# AlvDuino.net
KiCad netlist of a schematic drawn in EAGLE
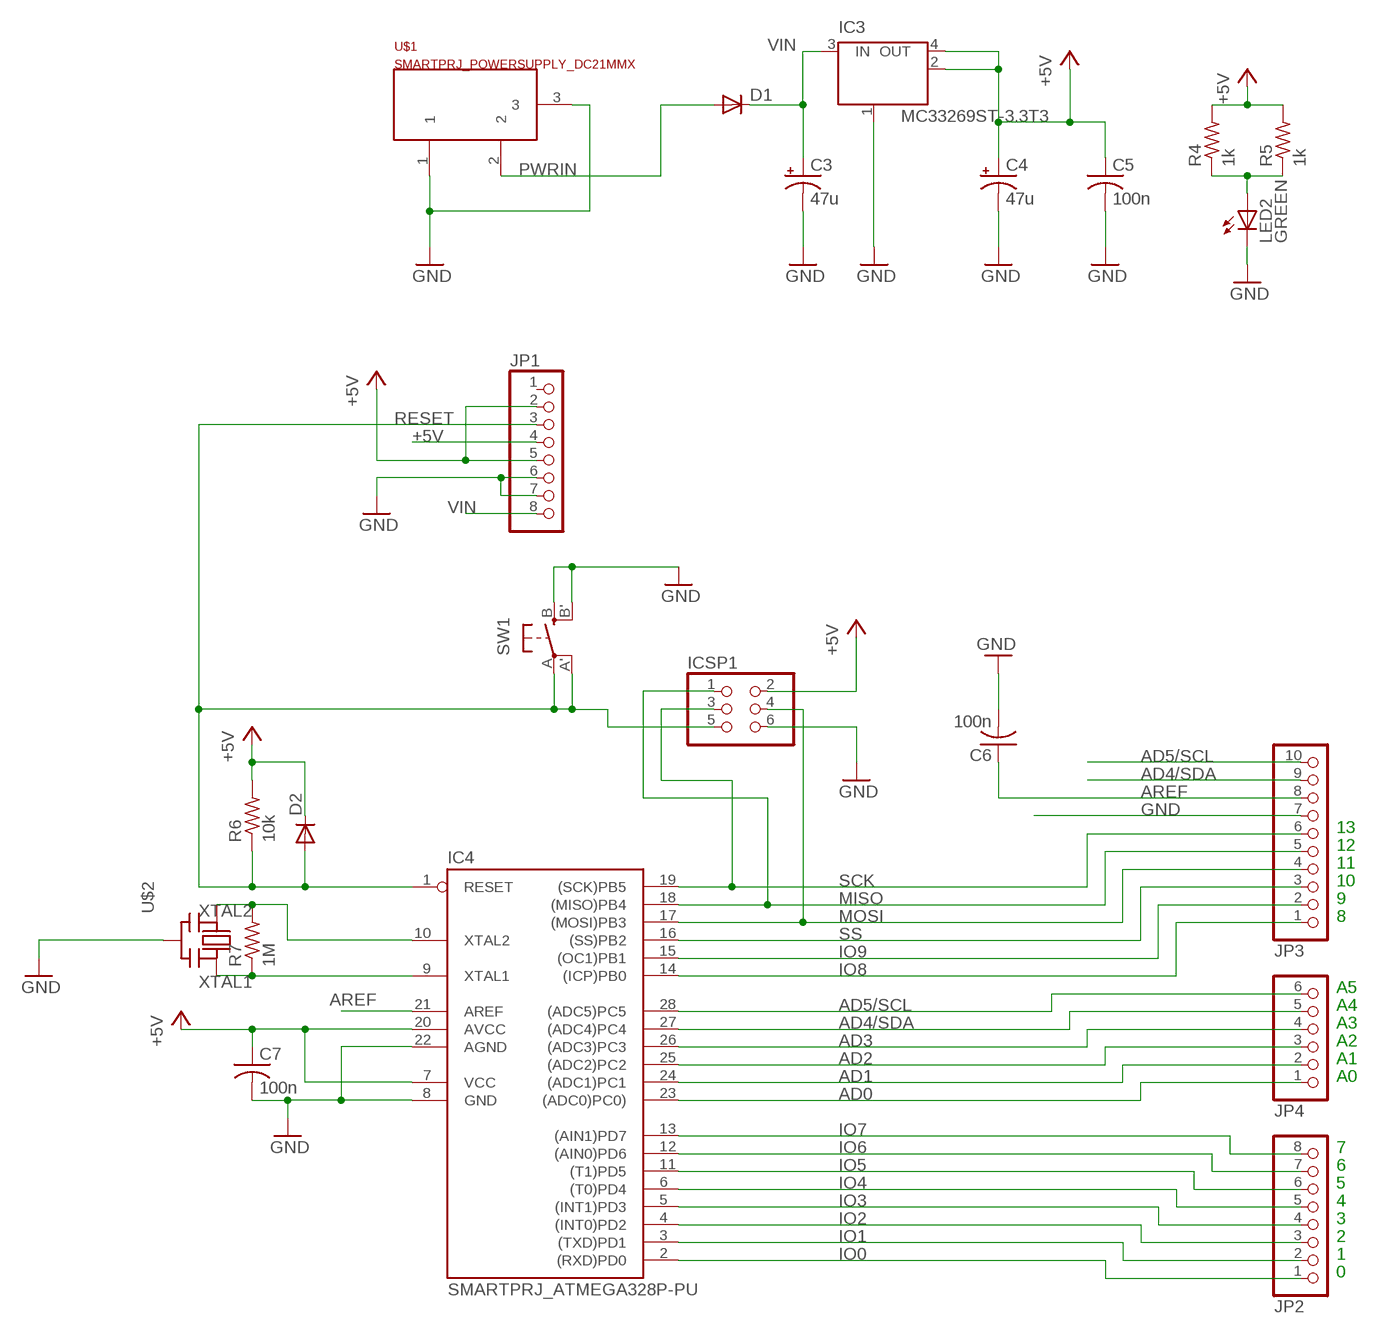
[diagram p0: schematic, sheet 1]

(export (version "E")
  (design (tool "Eeschema 10.0.6"))
  (components
    (comp (ref "C3")
      (value "47u")
      (footprint "eagle-import:PANASONIC_D")
      (libsource (lib "eagle-import") (part "CPOL-USD"))
    )
    (comp (ref "C4")
      (value "47u")
      (footprint "eagle-import:PANASONIC_D")
      (libsource (lib "eagle-import") (part "CPOL-USD"))
    )
    (comp (ref "C5")
      (value "100n")
      (footprint "eagle-import:C1206")
      (libsource (lib "eagle-import") (part "C-USC1206"))
    )
    (comp (ref "C6")
      (value "100n")
      (footprint "eagle-import:C1206")
      (libsource (lib "eagle-import") (part "C-USC1206"))
    )
    (comp (ref "C7")
      (value "100n")
      (footprint "eagle-import:C1206")
      (libsource (lib "eagle-import") (part "C-USC1206"))
    )
    (comp (ref "D1")
      (value "DIODE-DO214AA")
      (footprint "eagle-import:DO214AA")
      (libsource (lib "eagle-import") (part "DIODE-DO214AA"))
    )
    (comp (ref "D2")
      (value "DIODE-DO214AA")
      (footprint "eagle-import:DO214AA")
      (libsource (lib "eagle-import") (part "DIODE-DO214AA"))
    )
    (comp (ref "IC3")
      (value "MC33269ST-3.3T3")
      (footprint "eagle-import:SOT223")
      (libsource (lib "eagle-import") (part "MC33269ST-3.3T3"))
    )
    (comp (ref "IC4")
      (value "SMARTPRJ_ATMEGA328P-PU")
      (footprint "eagle-import:SMARTPRJ_DIL28-3")
      (libsource (lib "eagle-import") (part "SMARTPRJ_ATMEGA328P-PU"))
    )
    (comp (ref "ICSP1")
      (value "PINHD-2X3")
      (footprint "eagle-import:2X03")
      (libsource (lib "eagle-import") (part "PINHD-2X3"))
    )
    (comp (ref "JP1")
      (value "PINHD-1X8")
      (footprint "eagle-import:1X08")
      (libsource (lib "eagle-import") (part "PINHD-1X8"))
    )
    (comp (ref "JP2")
      (value "PINHD-1X8")
      (footprint "eagle-import:1X08")
      (libsource (lib "eagle-import") (part "PINHD-1X8"))
    )
    (comp (ref "JP3")
      (value "PINHD-1X10")
      (footprint "eagle-import:1X10")
      (libsource (lib "eagle-import") (part "PINHD-1X10"))
    )
    (comp (ref "JP4")
      (value "PINHD-1X6")
      (footprint "eagle-import:1X06")
      (libsource (lib "eagle-import") (part "PINHD-1X6"))
    )
    (comp (ref "LED2")
      (value "GREEN")
      (footprint "eagle-import:CHIPLED_1206")
      (libsource (lib "eagle-import") (part "LEDCHIPLED_1206"))
    )
    (comp (ref "R4")
      (value "1k")
      (footprint "eagle-import:R1206")
      (libsource (lib "eagle-import") (part "R-US_R1206"))
    )
    (comp (ref "R5")
      (value "1k")
      (footprint "eagle-import:R1206")
      (libsource (lib "eagle-import") (part "R-US_R1206"))
    )
    (comp (ref "R6")
      (value "10k")
      (footprint "eagle-import:R1206")
      (libsource (lib "eagle-import") (part "R-US_R1206"))
    )
    (comp (ref "R7")
      (value "1M")
      (footprint "eagle-import:R1206")
      (libsource (lib "eagle-import") (part "R-US_R1206"))
    )
    (comp (ref "SW1")
      (value "SPST_TACT-EVQQ2")
      (footprint "eagle-import:EVQ-Q2")
      (libsource (lib "eagle-import") (part "SPST_TACT-EVQQ2"))
    )
    (comp (ref "U$1")
      (value "SMARTPRJ_POWERSUPPLY_DC21MMX")
      (footprint "eagle-import:SMARTPRJ_POWERSUPPLY_DC-21MM")
      (libsource (lib "eagle-import") (part "SMARTPRJ_POWERSUPPLY_DC21MMX"))
    )
    (comp (ref "U$2")
      (value "CERMOSCILL-THM")
      (footprint "eagle-import:CERM_OSC")
      (libsource (lib "eagle-import") (part "CERMOSCILL-THM"))
    )
  )
  (nets
    (net (code "1") (name "+5V") (class "Default")
      (node (ref "C4") (pin "+") (pinfunction "+_+") (pintype "passive"))
      (node (ref "C5") (pin "1") (pinfunction "1_1") (pintype "passive"))
      (node (ref "C7") (pin "1") (pinfunction "1_1") (pintype "passive"))
      (node (ref "D2") (pin "C") (pinfunction "C_C") (pintype "passive"))
      (node (ref "IC3") (pin "2") (pinfunction "OUT_2") (pintype "passive"))
      (node (ref "IC3") (pin "4") (pinfunction "OUT_4") (pintype "passive"))
      (node (ref "IC4") (pin "20") (pinfunction "AVCC_20") (pintype "power_in"))
      (node (ref "IC4") (pin "7") (pinfunction "VCC_7") (pintype "power_in"))
      (node (ref "ICSP1") (pin "2") (pinfunction "2_2") (pintype "passive"))
      (node (ref "JP1") (pin "2") (pinfunction "2_2") (pintype "passive"))
      (node (ref "JP1") (pin "4") (pinfunction "4_4") (pintype "passive"))
      (node (ref "JP1") (pin "5") (pinfunction "5_5") (pintype "passive"))
      (node (ref "R4") (pin "2") (pinfunction "2_2") (pintype "passive"))
      (node (ref "R5") (pin "2") (pinfunction "2_2") (pintype "passive"))
      (node (ref "R6") (pin "2") (pinfunction "2_2") (pintype "passive"))
    )
    (net (code "2") (name "/AD0") (class "Default")
      (node (ref "IC4") (pin "23") (pinfunction "(ADC0)PC0)_23") (pintype "bidirectional"))
      (node (ref "JP4") (pin "1") (pinfunction "1_1") (pintype "passive"))
    )
    (net (code "3") (name "/AD1") (class "Default")
      (node (ref "IC4") (pin "24") (pinfunction "(ADC1)PC1_24") (pintype "bidirectional"))
      (node (ref "JP4") (pin "2") (pinfunction "2_2") (pintype "passive"))
    )
    (net (code "4") (name "/AD2") (class "Default")
      (node (ref "IC4") (pin "25") (pinfunction "(ADC2)PC2_25") (pintype "bidirectional"))
      (node (ref "JP4") (pin "3") (pinfunction "3_3") (pintype "passive"))
    )
    (net (code "5") (name "/AD3") (class "Default")
      (node (ref "IC4") (pin "26") (pinfunction "(ADC3)PC3_26") (pintype "bidirectional"))
      (node (ref "JP4") (pin "4") (pinfunction "4_4") (pintype "passive"))
    )
    (net (code "6") (name "/AD4{slash}SDA") (class "Default")
      (node (ref "IC4") (pin "27") (pinfunction "(ADC4)PC4_27") (pintype "bidirectional"))
      (node (ref "JP3") (pin "9") (pinfunction "9_9") (pintype "passive"))
      (node (ref "JP4") (pin "5") (pinfunction "5_5") (pintype "passive"))
    )
    (net (code "7") (name "/AD5{slash}SCL") (class "Default")
      (node (ref "IC4") (pin "28") (pinfunction "(ADC5)PC5_28") (pintype "bidirectional"))
      (node (ref "JP3") (pin "10") (pinfunction "10_10") (pintype "passive"))
      (node (ref "JP4") (pin "6") (pinfunction "6_6") (pintype "passive"))
    )
    (net (code "8") (name "/AREF") (class "Default")
      (node (ref "C6") (pin "1") (pinfunction "1_1") (pintype "passive"))
      (node (ref "IC4") (pin "21") (pinfunction "AREF_21") (pintype "passive"))
      (node (ref "JP3") (pin "8") (pinfunction "8_8") (pintype "passive"))
    )
    (net (code "9") (name "/IO0") (class "Default")
      (node (ref "IC4") (pin "2") (pinfunction "(RXD)PD0_2") (pintype "bidirectional"))
      (node (ref "JP2") (pin "1") (pinfunction "1_1") (pintype "passive"))
    )
    (net (code "10") (name "/IO1") (class "Default")
      (node (ref "IC4") (pin "3") (pinfunction "(TXD)PD1_3") (pintype "bidirectional"))
      (node (ref "JP2") (pin "2") (pinfunction "2_2") (pintype "passive"))
    )
    (net (code "11") (name "/IO2") (class "Default")
      (node (ref "IC4") (pin "4") (pinfunction "(INT0)PD2_4") (pintype "bidirectional"))
      (node (ref "JP2") (pin "3") (pinfunction "3_3") (pintype "passive"))
    )
    (net (code "12") (name "/IO3") (class "Default")
      (node (ref "IC4") (pin "5") (pinfunction "(INT1)PD3_5") (pintype "bidirectional"))
      (node (ref "JP2") (pin "4") (pinfunction "4_4") (pintype "passive"))
    )
    (net (code "13") (name "/IO4") (class "Default")
      (node (ref "IC4") (pin "6") (pinfunction "(T0)PD4_6") (pintype "bidirectional"))
      (node (ref "JP2") (pin "5") (pinfunction "5_5") (pintype "passive"))
    )
    (net (code "14") (name "/IO5") (class "Default")
      (node (ref "IC4") (pin "11") (pinfunction "(T1)PD5_11") (pintype "bidirectional"))
      (node (ref "JP2") (pin "6") (pinfunction "6_6") (pintype "passive"))
    )
    (net (code "15") (name "/IO6") (class "Default")
      (node (ref "IC4") (pin "12") (pinfunction "(AIN0)PD6_12") (pintype "bidirectional"))
      (node (ref "JP2") (pin "7") (pinfunction "7_7") (pintype "passive"))
    )
    (net (code "16") (name "/IO7") (class "Default")
      (node (ref "IC4") (pin "13") (pinfunction "(AIN1)PD7_13") (pintype "bidirectional"))
      (node (ref "JP2") (pin "8") (pinfunction "8_8") (pintype "passive"))
    )
    (net (code "17") (name "/IO8") (class "Default")
      (node (ref "IC4") (pin "14") (pinfunction "(ICP)PB0_14") (pintype "bidirectional"))
      (node (ref "JP3") (pin "1") (pinfunction "1_1") (pintype "passive"))
    )
    (net (code "18") (name "/IO9") (class "Default")
      (node (ref "IC4") (pin "15") (pinfunction "(OC1)PB1_15") (pintype "bidirectional"))
      (node (ref "JP3") (pin "2") (pinfunction "2_2") (pintype "passive"))
    )
    (net (code "19") (name "/MISO") (class "Default")
      (node (ref "IC4") (pin "18") (pinfunction "(MISO)PB4_18") (pintype "bidirectional"))
      (node (ref "ICSP1") (pin "1") (pinfunction "1_1") (pintype "passive"))
      (node (ref "JP3") (pin "5") (pinfunction "5_5") (pintype "passive"))
    )
    (net (code "20") (name "/MOSI") (class "Default")
      (node (ref "IC4") (pin "17") (pinfunction "(MOSI)PB3_17") (pintype "bidirectional"))
      (node (ref "ICSP1") (pin "4") (pinfunction "4_4") (pintype "passive"))
      (node (ref "JP3") (pin "4") (pinfunction "4_4") (pintype "passive"))
    )
    (net (code "21") (name "/PWRIN") (class "Default")
      (node (ref "D1") (pin "A") (pinfunction "A_A") (pintype "passive"))
      (node (ref "U$1") (pin "2") (pinfunction "2_2") (pintype "power_in"))
    )
    (net (code "22") (name "/RESET") (class "Default")
      (node (ref "D2") (pin "A") (pinfunction "A_A") (pintype "passive"))
      (node (ref "IC4") (pin "1") (pinfunction "RESET_1") (pintype "input"))
      (node (ref "ICSP1") (pin "5") (pinfunction "5_5") (pintype "passive"))
      (node (ref "JP1") (pin "3") (pinfunction "3_3") (pintype "passive"))
      (node (ref "R6") (pin "1") (pinfunction "1_1") (pintype "passive"))
      (node (ref "SW1") (pin "A") (pinfunction "P_A") (pintype "passive"))
      (node (ref "SW1") (pin "A'") (pinfunction "P1_A'") (pintype "passive"))
    )
    (net (code "23") (name "/SCK") (class "Default")
      (node (ref "IC4") (pin "19") (pinfunction "(SCK)PB5_19") (pintype "bidirectional"))
      (node (ref "ICSP1") (pin "3") (pinfunction "3_3") (pintype "passive"))
      (node (ref "JP3") (pin "6") (pinfunction "6_6") (pintype "passive"))
    )
    (net (code "24") (name "/SS") (class "Default")
      (node (ref "IC4") (pin "16") (pinfunction "(SS)PB2_16") (pintype "bidirectional"))
      (node (ref "JP3") (pin "3") (pinfunction "3_3") (pintype "passive"))
    )
    (net (code "25") (name "/VIN") (class "Default")
      (node (ref "C3") (pin "+") (pinfunction "+_+") (pintype "passive"))
      (node (ref "D1") (pin "C") (pinfunction "C_C") (pintype "passive"))
      (node (ref "IC3") (pin "3") (pinfunction "IN_3") (pintype "input"))
      (node (ref "JP1") (pin "8") (pinfunction "8_8") (pintype "passive"))
    )
    (net (code "26") (name "/XTAL1") (class "Default")
      (node (ref "IC4") (pin "9") (pinfunction "XTAL1_9") (pintype "bidirectional"))
      (node (ref "R7") (pin "1") (pinfunction "1_1") (pintype "passive"))
      (node (ref "U$2") (pin "P$3") (pinfunction "OUT_P$3") (pintype "bidirectional"))
    )
    (net (code "27") (name "/XTAL2") (class "Default")
      (node (ref "IC4") (pin "10") (pinfunction "XTAL2_10") (pintype "bidirectional"))
      (node (ref "R7") (pin "2") (pinfunction "2_2") (pintype "passive"))
      (node (ref "U$2") (pin "P$1") (pinfunction "IN_P$1") (pintype "bidirectional"))
    )
    (net (code "28") (name "GND") (class "Default")
      (node (ref "C3") (pin "-") (pinfunction "-_-") (pintype "passive"))
      (node (ref "C4") (pin "-") (pinfunction "-_-") (pintype "passive"))
      (node (ref "C5") (pin "2") (pinfunction "2_2") (pintype "passive"))
      (node (ref "C6") (pin "2") (pinfunction "2_2") (pintype "passive"))
      (node (ref "C7") (pin "2") (pinfunction "2_2") (pintype "passive"))
      (node (ref "IC3") (pin "1") (pinfunction "GND/ADJ_1") (pintype "input"))
      (node (ref "IC4") (pin "22") (pinfunction "AGND_22") (pintype "power_in"))
      (node (ref "IC4") (pin "8") (pinfunction "GND_8") (pintype "power_in"))
      (node (ref "ICSP1") (pin "6") (pinfunction "6_6") (pintype "passive"))
      (node (ref "JP1") (pin "6") (pinfunction "6_6") (pintype "passive"))
      (node (ref "JP1") (pin "7") (pinfunction "7_7") (pintype "passive"))
      (node (ref "JP3") (pin "7") (pinfunction "7_7") (pintype "passive"))
      (node (ref "LED2") (pin "C") (pinfunction "C_C") (pintype "passive"))
      (node (ref "SW1") (pin "B") (pinfunction "S_B") (pintype "passive"))
      (node (ref "SW1") (pin "B'") (pinfunction "S1_B'") (pintype "passive"))
      (node (ref "U$1") (pin "1") (pinfunction "1_1") (pintype "power_in"))
      (node (ref "U$1") (pin "3") (pinfunction "3_3") (pintype "power_in"))
      (node (ref "U$2") (pin "P$2") (pinfunction "GND_P$2") (pintype "bidirectional"))
    )
    (net (code "29") (name "Net-(LED2-PadA)") (class "Default")
      (node (ref "LED2") (pin "A") (pinfunction "A_A") (pintype "passive"))
      (node (ref "R4") (pin "1") (pinfunction "1_1") (pintype "passive"))
      (node (ref "R5") (pin "1") (pinfunction "1_1") (pintype "passive"))
    )
    (net (code "30") (name "unconnected-(JP1-Pad1)") (class "Default")
      (node (ref "JP1") (pin "1") (pinfunction "1_1") (pintype "passive"))
    )
  )
)
